# EthernetRMIIPHY.net
KiCad netlist of a schematic drawn in Altium Designer
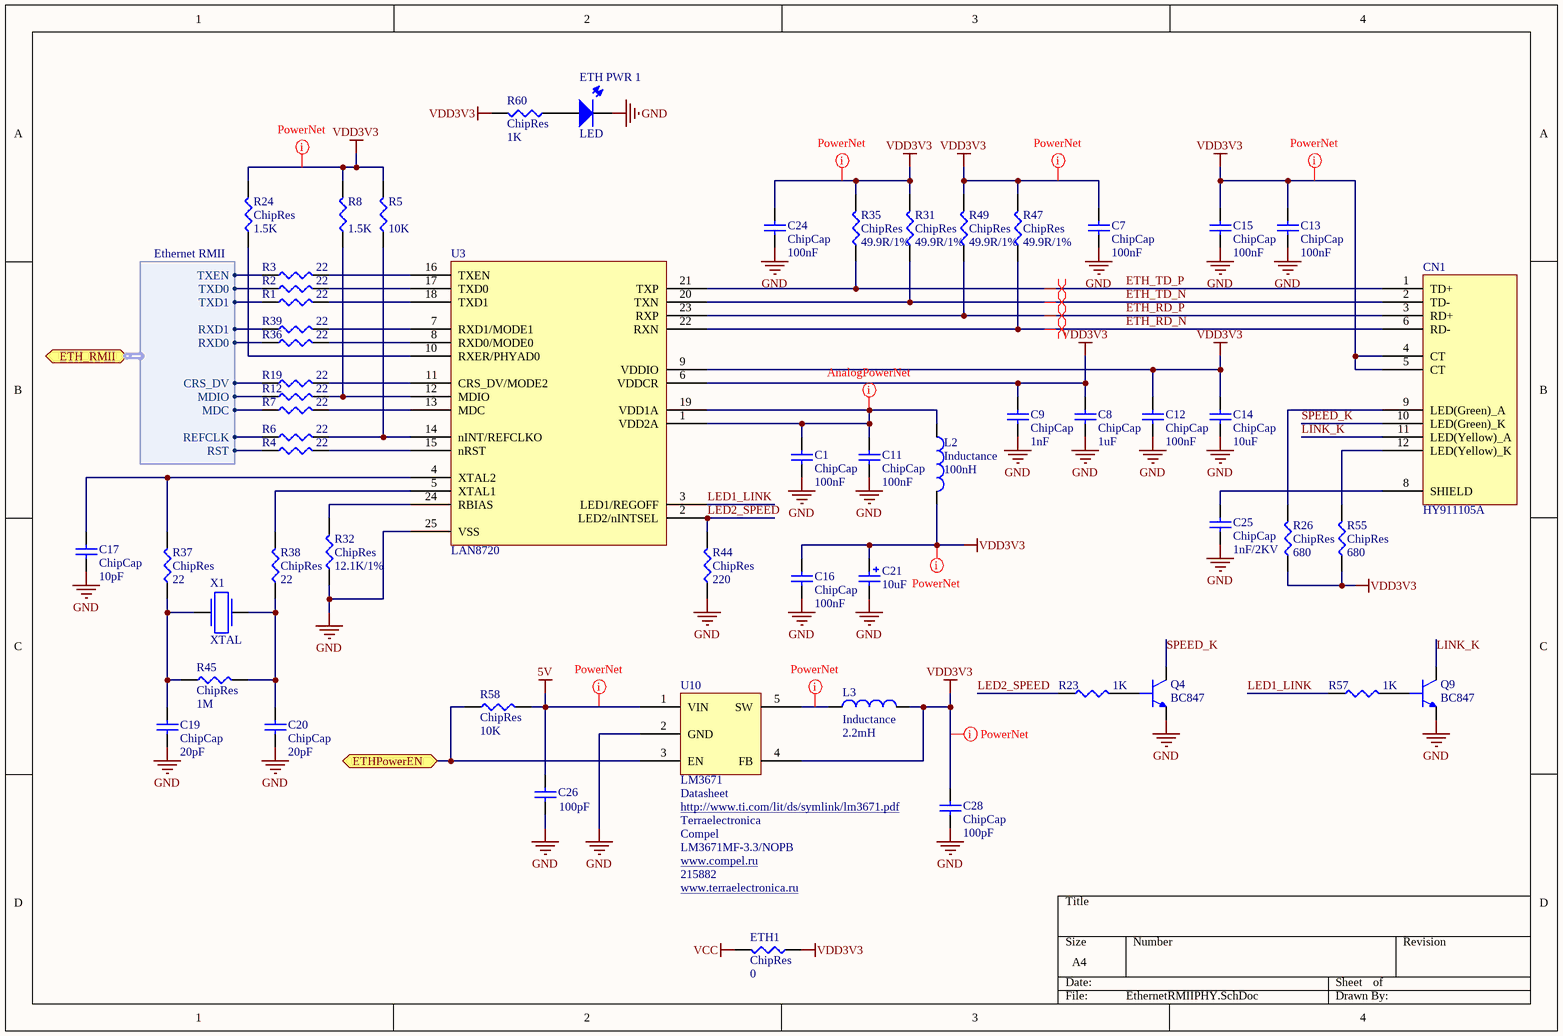
[diagram p0: EthernetRMIIPHY.SchDoc]

(export (version "E")
  (design (tool "Eeschema 10.0.6"))
  (components
    (comp (ref "C1")
      (value "ChipCap")
      (footprint "CAP0805")
      (description "Capacitor")
      (fields (field (name "ALTIUM_VALUE") "100nF") (field (name "PUBLISHER") "Altium Limited"))
      (libsource (lib "Common Devices") (part "ChipCap"))
    )
    (comp (ref "C7")
      (value "ChipCap")
      (footprint "CAP0805")
      (description "Capacitor")
      (fields (field (name "ALTIUM_VALUE") "100nF") (field (name "PUBLISHER") "Altium Limited"))
      (libsource (lib "Common Devices") (part "ChipCap"))
    )
    (comp (ref "C8")
      (value "ChipCap")
      (footprint "CAP0805")
      (description "Capacitor")
      (fields (field (name "ALTIUM_VALUE") "1uF") (field (name "PUBLISHER") "Altium Limited"))
      (libsource (lib "Common Devices") (part "ChipCap"))
    )
    (comp (ref "C9")
      (value "ChipCap")
      (footprint "CAP0805")
      (description "Capacitor")
      (fields (field (name "ALTIUM_VALUE") "1nF") (field (name "PUBLISHER") "Altium Limited"))
      (libsource (lib "Common Devices") (part "ChipCap"))
    )
    (comp (ref "C11")
      (value "ChipCap")
      (footprint "CAP0805")
      (description "Capacitor")
      (fields (field (name "ALTIUM_VALUE") "100nF") (field (name "PUBLISHER") "Altium Limited"))
      (libsource (lib "Common Devices") (part "ChipCap"))
    )
    (comp (ref "C12")
      (value "ChipCap")
      (footprint "CAP0805")
      (description "Capacitor")
      (fields (field (name "ALTIUM_VALUE") "100nF") (field (name "PUBLISHER") "Altium Limited"))
      (libsource (lib "Common Devices") (part "ChipCap"))
    )
    (comp (ref "C13")
      (value "ChipCap")
      (footprint "CAP0805")
      (description "Capacitor")
      (fields (field (name "ALTIUM_VALUE") "100nF") (field (name "PUBLISHER") "Altium Limited"))
      (libsource (lib "Common Devices") (part "ChipCap"))
    )
    (comp (ref "C14")
      (value "ChipCap")
      (footprint "CAP0805")
      (description "Capacitor")
      (fields (field (name "ALTIUM_VALUE") "10uF") (field (name "PUBLISHER") "Altium Limited"))
      (libsource (lib "Common Devices") (part "ChipCap"))
    )
    (comp (ref "C15")
      (value "ChipCap")
      (footprint "CAP0805")
      (description "Capacitor")
      (fields (field (name "ALTIUM_VALUE") "100nF") (field (name "PUBLISHER") "Altium Limited"))
      (libsource (lib "Common Devices") (part "ChipCap"))
    )
    (comp (ref "C16")
      (value "ChipCap")
      (footprint "CAP0805")
      (description "Capacitor")
      (fields (field (name "ALTIUM_VALUE") "100nF") (field (name "PUBLISHER") "Altium Limited"))
      (libsource (lib "Common Devices") (part "ChipCap"))
    )
    (comp (ref "C17")
      (value "ChipCap")
      (footprint "CAP0805")
      (description "Capacitor")
      (fields (field (name "ALTIUM_VALUE") "10pF") (field (name "PUBLISHER") "Altium Limited"))
      (libsource (lib "Common Devices") (part "ChipCap"))
    )
    (comp (ref "C19")
      (value "ChipCap")
      (footprint "CAP0805")
      (description "Capacitor")
      (fields (field (name "ALTIUM_VALUE") "20pF") (field (name "PUBLISHER") "Altium Limited"))
      (libsource (lib "Common Devices") (part "ChipCap"))
    )
    (comp (ref "C20")
      (value "ChipCap")
      (footprint "CAP0805")
      (description "Capacitor")
      (fields (field (name "ALTIUM_VALUE") "20pF") (field (name "PUBLISHER") "Altium Limited"))
      (libsource (lib "Common Devices") (part "ChipCap"))
    )
    (comp (ref "C21")
      (value "10uF")
      (footprint "CAPC7343")
      (description "Polarized Capacitor (Radial)")
      (fields (field (name "Comment") "Cap Pol SMD"))
      (libsource (lib "Common Devices") (part "Cap Pol Chip"))
    )
    (comp (ref "C24")
      (value "ChipCap")
      (footprint "CAP0805")
      (description "Capacitor")
      (fields (field (name "ALTIUM_VALUE") "100nF") (field (name "PUBLISHER") "Altium Limited"))
      (libsource (lib "Common Devices") (part "ChipCap"))
    )
    (comp (ref "C25")
      (value "ChipCap")
      (footprint "CAP0805")
      (description "Capacitor")
      (fields (field (name "ALTIUM_VALUE") "1nF/2KV") (field (name "PUBLISHER") "Altium Limited"))
      (libsource (lib "Common Devices") (part "ChipCap"))
    )
    (comp (ref "C26")
      (value "100pF")
      (footprint "CAP1210")
      (description "Capacitor")
      (fields (field (name "Comment") "ChipCap") (field (name "PUBLISHER") "Altium Limited"))
      (libsource (lib "Common Devices") (part "ChipCap"))
    )
    (comp (ref "C28")
      (value "ChipCap")
      (footprint "CAP1210")
      (description "Capacitor")
      (fields (field (name "ALTIUM_VALUE") "100pF") (field (name "PUBLISHER") "Altium Limited"))
      (libsource (lib "Common Devices") (part "ChipCap"))
    )
    (comp (ref "CN1")
      (value "HY911105A")
      (footprint "HR911105A")
      (libsource (lib "Connectors") (part "HY911105A"))
    )
    (comp (ref "ETH PWR 1") (value "LED") (footprint "PLCC-2") (libsource (lib "LEDs") (part "LED0603")))
    (comp (ref "ETH1")
      (value "ChipRes")
      (footprint "RES0805")
      (description "Chip resistor")
      (fields (field (name "ALTIUM_VALUE") "0"))
      (libsource (lib "Common Devices") (part "ChipRes"))
    )
    (comp (ref "L2")
      (value "Inductance")
      (footprint "CM45")
      (fields (field (name "ALTIUM_VALUE") "100nH"))
      (libsource (lib "") (part "ChipInductance_1"))
    )
    (comp (ref "L3")
      (value "Inductance")
      (footprint "CDRH2D14")
      (fields (field (name "ALTIUM_VALUE") "2.2mH"))
      (libsource (lib "Common Devices") (part "ChipInductance"))
    )
    (comp (ref "Q4")
      (value "BC847")
      (footprint "BJT:SOT23")
      (description "NPN transistor")
      (libsource (lib "BJT") (part "BC847"))
    )
    (comp (ref "Q9")
      (value "BC847")
      (footprint "BJT:SOT23")
      (description "NPN transistor")
      (libsource (lib "BJT") (part "BC847"))
    )
    (comp (ref "R1")
      (value "22")
      (footprint "RES0805")
      (description "Chip resistor")
      (fields (field (name "Comment") "ChipRes"))
      (libsource (lib "Common Devices") (part "ChipRes"))
    )
    (comp (ref "R2")
      (value "22")
      (footprint "RES0805")
      (description "Chip resistor")
      (fields (field (name "Comment") "ChipRes"))
      (libsource (lib "Common Devices") (part "ChipRes"))
    )
    (comp (ref "R3")
      (value "22")
      (footprint "RES0805")
      (description "Chip resistor")
      (fields (field (name "Comment") "ChipRes"))
      (libsource (lib "Common Devices") (part "ChipRes"))
    )
    (comp (ref "R4")
      (value "22")
      (footprint "RES0805")
      (description "Chip resistor")
      (fields (field (name "Comment") "ChipRes"))
      (libsource (lib "Common Devices") (part "ChipRes"))
    )
    (comp (ref "R5")
      (value "10K")
      (footprint "RES0805")
      (description "Chip resistor")
      (fields (field (name "Comment") "ChipRes"))
      (libsource (lib "Common Devices") (part "ChipRes"))
    )
    (comp (ref "R6")
      (value "22")
      (footprint "RES0805")
      (description "Chip resistor")
      (fields (field (name "Comment") "ChipRes"))
      (libsource (lib "Common Devices") (part "ChipRes"))
    )
    (comp (ref "R7")
      (value "22")
      (footprint "RES0805")
      (description "Chip resistor")
      (fields (field (name "Comment") "ChipRes"))
      (libsource (lib "Common Devices") (part "ChipRes"))
    )
    (comp (ref "R8")
      (value "1.5K")
      (footprint "RES0805")
      (description "Chip resistor")
      (fields (field (name "Comment") "ChipRes"))
      (libsource (lib "Common Devices") (part "ChipRes"))
    )
    (comp (ref "R12")
      (value "22")
      (footprint "RES0805")
      (description "Chip resistor")
      (fields (field (name "Comment") "ChipRes"))
      (libsource (lib "Common Devices") (part "ChipRes"))
    )
    (comp (ref "R19")
      (value "22")
      (footprint "RES0805")
      (description "Chip resistor")
      (fields (field (name "Comment") "ChipRes"))
      (libsource (lib "Common Devices") (part "ChipRes"))
    )
    (comp (ref "R23")
      (value "1K")
      (footprint "RES0805")
      (description "Chip resistor")
      (fields (field (name "Comment") "ChipRes"))
      (libsource (lib "Common Devices") (part "ChipRes"))
    )
    (comp (ref "R24")
      (value "ChipRes")
      (footprint "RES0805")
      (description "Chip resistor")
      (fields (field (name "ALTIUM_VALUE") "1.5K"))
      (libsource (lib "Common Devices") (part "ChipRes"))
    )
    (comp (ref "R26")
      (value "ChipRes")
      (footprint "RES0805")
      (description "Chip resistor")
      (fields (field (name "ALTIUM_VALUE") "680"))
      (libsource (lib "Common Devices") (part "ChipRes"))
    )
    (comp (ref "R31")
      (value "ChipRes")
      (footprint "RES0805")
      (description "Chip resistor")
      (fields (field (name "ALTIUM_VALUE") "49.9R/1%"))
      (libsource (lib "Common Devices") (part "ChipRes"))
    )
    (comp (ref "R32")
      (value "ChipRes")
      (footprint "RES0805")
      (description "Chip resistor")
      (fields (field (name "ALTIUM_VALUE") "12.1K/1%"))
      (libsource (lib "Common Devices") (part "ChipRes"))
    )
    (comp (ref "R35")
      (value "ChipRes")
      (footprint "RES0805")
      (description "Chip resistor")
      (fields (field (name "ALTIUM_VALUE") "49.9R/1%"))
      (libsource (lib "Common Devices") (part "ChipRes"))
    )
    (comp (ref "R36")
      (value "22")
      (footprint "RES0805")
      (description "Chip resistor")
      (fields (field (name "Comment") "ChipRes"))
      (libsource (lib "Common Devices") (part "ChipRes"))
    )
    (comp (ref "R37")
      (value "ChipRes")
      (footprint "RES0805")
      (description "Chip resistor")
      (fields (field (name "ALTIUM_VALUE") "22"))
      (libsource (lib "Common Devices") (part "ChipRes"))
    )
    (comp (ref "R38")
      (value "ChipRes")
      (footprint "RES0805")
      (description "Chip resistor")
      (fields (field (name "ALTIUM_VALUE") "22"))
      (libsource (lib "Common Devices") (part "ChipRes"))
    )
    (comp (ref "R39")
      (value "22")
      (footprint "RES0805")
      (description "Chip resistor")
      (fields (field (name "Comment") "ChipRes"))
      (libsource (lib "Common Devices") (part "ChipRes"))
    )
    (comp (ref "R44")
      (value "ChipRes")
      (footprint "RES0805")
      (description "Chip resistor")
      (fields (field (name "ALTIUM_VALUE") "220"))
      (libsource (lib "Common Devices") (part "ChipRes"))
    )
    (comp (ref "R45")
      (value "ChipRes")
      (footprint "RES0805")
      (description "Chip resistor")
      (fields (field (name "ALTIUM_VALUE") "1M"))
      (libsource (lib "Common Devices") (part "ChipRes"))
    )
    (comp (ref "R47")
      (value "ChipRes")
      (footprint "RES0805")
      (description "Chip resistor")
      (fields (field (name "ALTIUM_VALUE") "49.9R/1%"))
      (libsource (lib "Common Devices") (part "ChipRes"))
    )
    (comp (ref "R49")
      (value "ChipRes")
      (footprint "RES0805")
      (description "Chip resistor")
      (fields (field (name "ALTIUM_VALUE") "49.9R/1%"))
      (libsource (lib "Common Devices") (part "ChipRes"))
    )
    (comp (ref "R55")
      (value "ChipRes")
      (footprint "RES0805")
      (description "Chip resistor")
      (fields (field (name "ALTIUM_VALUE") "680"))
      (libsource (lib "Common Devices") (part "ChipRes"))
    )
    (comp (ref "R57")
      (value "1K")
      (footprint "RES0805")
      (description "Chip resistor")
      (fields (field (name "Comment") "ChipRes"))
      (libsource (lib "Common Devices") (part "ChipRes"))
    )
    (comp (ref "R58")
      (value "ChipRes")
      (footprint "RES0805")
      (description "Chip resistor")
      (fields (field (name "ALTIUM_VALUE") "10K"))
      (libsource (lib "Common Devices") (part "ChipRes"))
    )
    (comp (ref "R60")
      (value "ChipRes")
      (footprint "RES0805")
      (description "Chip resistor")
      (fields (field (name "ALTIUM_VALUE") "1K"))
      (libsource (lib "Common Devices") (part "ChipRes"))
    )
    (comp (ref "U3")
      (value "LAN8720")
      (footprint "QFN50P375X375X85_HS-25N")
      (description "Small Footprint RMII 10/100 Ethernet  Transceiver")
      (libsource (lib "SMSC Microchip Ethernet Driver") (part "LAM8720"))
    )
    (comp (ref "U10")
      (value "LM3671")
      (footprint "SOT23-5")
      (description "600-mA Step-Down DC-DC Converter")
      (fields
        (field (name "COMPONENTLINK1DESCRIPTION") "Datasheet")
        (field (name "COMPONENTLINK1URL") "http://www.ti.com/lit/ds/symlink/lm3671.pdf")
        (field (name "SUPPLIER 1") "Terraelectronica")
        (field (name "SUPPLIER 2") "Compel")
        (field (name "SUPPLIER PART NUMBER 2") "LM3671MF-3.3/NOPB")
        (field (name "SUPPLIER URL 2") "www.compel.ru")
        (field (name "SUPPLIER PART NUMBER 1") "215882")
        (field (name "SUPPLIER URL 1") "www.terraelectronica.ru")
      )
      (libsource (lib "TI DC-DC Convertors") (part "LM3671MF"))
    )
    (comp (ref "X1")
      (value "XTAL")
      (footprint "BCY-W2/E4.7")
      (description "Quartz crystall oscillator")
      (libsource (lib "Common Devices") (part "Crystall oscillator"))
    )
  )
  (nets
    (net (code "3") (name "/CRS_DV") (class "Default") (node (ref "R19") (pin "1") (pintype "passive")))
    (net (code "4") (name "/ETHPowerEN") (class "Default")
      (node (ref "R58") (pin "1") (pintype "passive"))
      (node (ref "U10") (pin "3") (pinfunction "EN_3") (pintype "passive"))
    )
    (net (code "5") (name "/ETH_RD_N") (class "Default")
      (node (ref "CN1") (pin "6") (pinfunction "RD-_6") (pintype "passive"))
      (node (ref "R47") (pin "1") (pintype "passive"))
      (node (ref "U3") (pin "22") (pinfunction "RXN_22") (pintype "passive"))
    )
    (net (code "6") (name "/ETH_RD_P") (class "Default")
      (node (ref "CN1") (pin "3") (pinfunction "RD+_3") (pintype "passive"))
      (node (ref "R49") (pin "1") (pintype "passive"))
      (node (ref "U3") (pin "23") (pinfunction "RXP_23") (pintype "passive"))
    )
    (net (code "7") (name "/ETH_TD_N") (class "Default")
      (node (ref "CN1") (pin "2") (pinfunction "TD-_2") (pintype "passive"))
      (node (ref "R31") (pin "1") (pintype "passive"))
      (node (ref "U3") (pin "20") (pinfunction "TXN_20") (pintype "passive"))
    )
    (net (code "8") (name "/ETH_TD_P") (class "Default")
      (node (ref "CN1") (pin "1") (pinfunction "TD+_1") (pintype "passive"))
      (node (ref "R35") (pin "1") (pintype "passive"))
      (node (ref "U3") (pin "21") (pinfunction "TXP_21") (pintype "passive"))
    )
    (net (code "9") (name "/LED1_LINK") (class "Default")
      (node (ref "R57") (pin "1") (pintype "passive"))
      (node (ref "U3") (pin "3") (pinfunction "LED1/REGOFF_3") (pintype "passive"))
    )
    (net (code "10") (name "/LED2_SPEED") (class "Default")
      (node (ref "R23") (pin "1") (pintype "passive"))
      (node (ref "R44") (pin "2") (pintype "passive"))
      (node (ref "U3") (pin "2") (pinfunction "LED2/nINTSEL_2") (pintype "passive"))
    )
    (net (code "11") (name "/LINK_K") (class "Default")
      (node (ref "CN1") (pin "11") (pinfunction "LED(Yellow)_A_11") (pintype "passive"))
      (node (ref "Q9") (pin "3") (pinfunction "3_3") (pintype "passive"))
    )
    (net (code "12") (name "/MDC") (class "Default") (node (ref "R7") (pin "1") (pintype "passive")))
    (net (code "13") (name "/MDIO") (class "Default") (node (ref "R12") (pin "1") (pintype "passive")))
    (net (code "14") (name "/REFCLK") (class "Default") (node (ref "R6") (pin "1") (pintype "passive")))
    (net (code "15") (name "/RST") (class "Default") (node (ref "R4") (pin "1") (pintype "passive")))
    (net (code "16") (name "/RXD0") (class "Default") (node (ref "R36") (pin "1") (pintype "passive")))
    (net (code "17") (name "/RXD1") (class "Default") (node (ref "R39") (pin "1") (pintype "passive")))
    (net (code "18") (name "/SPEED_K") (class "Default")
      (node (ref "CN1") (pin "10") (pinfunction "LED(Green)_K_10") (pintype "passive"))
      (node (ref "Q4") (pin "3") (pinfunction "3_3") (pintype "passive"))
    )
    (net (code "19") (name "/TXD0") (class "Default") (node (ref "R2") (pin "1") (pintype "passive")))
    (net (code "20") (name "/TXD1") (class "Default") (node (ref "R1") (pin "1") (pintype "passive")))
    (net (code "21") (name "/TXEN") (class "Default") (node (ref "R3") (pin "1") (pintype "passive")))
    (net (code "23") (name "5V") (class "Default")
      (node (ref "C26") (pin "2") (pinfunction "2_2") (pintype "passive"))
      (node (ref "R58") (pin "2") (pintype "passive"))
      (node (ref "U10") (pin "1") (pinfunction "VIN_1") (pintype "passive"))
    )
    (net (code "24") (name "GND") (class "Default")
      (node (ref "C1") (pin "1") (pinfunction "1_1") (pintype "passive"))
      (node (ref "C11") (pin "1") (pinfunction "1_1") (pintype "passive"))
      (node (ref "C12") (pin "1") (pinfunction "1_1") (pintype "passive"))
      (node (ref "C13") (pin "1") (pinfunction "1_1") (pintype "passive"))
      (node (ref "C14") (pin "1") (pinfunction "1_1") (pintype "passive"))
      (node (ref "C15") (pin "1") (pinfunction "1_1") (pintype "passive"))
      (node (ref "C16") (pin "1") (pinfunction "1_1") (pintype "passive"))
      (node (ref "C17") (pin "1") (pinfunction "1_1") (pintype "passive"))
      (node (ref "C19") (pin "1") (pinfunction "1_1") (pintype "passive"))
      (node (ref "C20") (pin "1") (pinfunction "1_1") (pintype "passive"))
      (node (ref "C21") (pin "2") (pinfunction "2_2") (pintype "passive"))
      (node (ref "C24") (pin "1") (pinfunction "1_1") (pintype "passive"))
      (node (ref "C25") (pin "1") (pinfunction "1_1") (pintype "passive"))
      (node (ref "C26") (pin "1") (pinfunction "1_1") (pintype "passive"))
      (node (ref "C28") (pin "1") (pinfunction "1_1") (pintype "passive"))
      (node (ref "C7") (pin "1") (pinfunction "1_1") (pintype "passive"))
      (node (ref "C8") (pin "1") (pinfunction "1_1") (pintype "passive"))
      (node (ref "C9") (pin "1") (pinfunction "1_1") (pintype "passive"))
      (node (ref "ETH PWR 1") (pin "1") (pinfunction "1_1") (pintype "passive"))
      (node (ref "Q4") (pin "2") (pinfunction "2_2") (pintype "passive"))
      (node (ref "Q9") (pin "2") (pinfunction "2_2") (pintype "passive"))
      (node (ref "R32") (pin "1") (pintype "passive"))
      (node (ref "R44") (pin "1") (pintype "passive"))
      (node (ref "U10") (pin "2") (pinfunction "GND_2") (pintype "passive"))
      (node (ref "U3") (pin "25") (pinfunction "VSS_25") (pintype "passive"))
    )
    (net (code "25") (name "Net-(C19-Pad2)") (class "Default")
      (node (ref "C19") (pin "2") (pinfunction "2_2") (pintype "passive"))
      (node (ref "R37") (pin "1") (pintype "passive"))
      (node (ref "R45") (pin "1") (pintype "passive"))
      (node (ref "X1") (pin "1") (pinfunction "1_1") (pintype "passive"))
    )
    (net (code "26") (name "Net-(C20-Pad2)") (class "Default")
      (node (ref "C20") (pin "2") (pinfunction "2_2") (pintype "passive"))
      (node (ref "R38") (pin "1") (pintype "passive"))
      (node (ref "R45") (pin "2") (pintype "passive"))
      (node (ref "X1") (pin "2") (pinfunction "2_2") (pintype "passive"))
    )
    (net (code "27") (name "Net-(CN1-LED(Green)_A)") (class "Default")
      (node (ref "CN1") (pin "9") (pinfunction "LED(Green)_A_9") (pintype "passive"))
      (node (ref "R26") (pin "2") (pintype "passive"))
    )
    (net (code "28") (name "Net-(CN1-LED(Yellow)_K)") (class "Default")
      (node (ref "CN1") (pin "12") (pinfunction "LED(Yellow)_K_12") (pintype "passive"))
      (node (ref "R55") (pin "2") (pintype "passive"))
    )
    (net (code "29") (name "Net-(CN1-SHIELD)") (class "Default")
      (node (ref "C25") (pin "2") (pinfunction "2_2") (pintype "passive"))
      (node (ref "CN1") (pin "8") (pinfunction "SHIELD_8") (pintype "passive"))
    )
    (net (code "30") (name "Net-(ETH PWR 1-Pad2)") (class "Default")
      (node (ref "ETH PWR 1") (pin "2") (pinfunction "2_2") (pintype "passive"))
      (node (ref "R60") (pin "1") (pintype "passive"))
    )
    (net (code "31") (name "Net-(Q4-Pad1)") (class "Default")
      (node (ref "Q4") (pin "1") (pinfunction "1_1") (pintype "passive"))
      (node (ref "R23") (pin "2") (pintype "passive"))
    )
    (net (code "32") (name "Net-(Q9-Pad1)") (class "Default")
      (node (ref "Q9") (pin "1") (pinfunction "1_1") (pintype "passive"))
      (node (ref "R57") (pin "2") (pintype "passive"))
    )
    (net (code "33") (name "Net-(U3-CRS_DV{slash}MODE2)") (class "Default")
      (node (ref "R19") (pin "2") (pintype "passive"))
      (node (ref "U3") (pin "11") (pinfunction "CRS_DV/MODE2_11") (pintype "passive"))
    )
    (net (code "34") (name "Net-(U3-MDC)") (class "Default")
      (node (ref "R7") (pin "2") (pintype "passive"))
      (node (ref "U3") (pin "13") (pinfunction "MDC_13") (pintype "passive"))
    )
    (net (code "35") (name "Net-(U3-MDIO)") (class "Default")
      (node (ref "R12") (pin "2") (pintype "passive"))
      (node (ref "R8") (pin "1") (pintype "passive"))
      (node (ref "U3") (pin "12") (pinfunction "MDIO_12") (pintype "passive"))
    )
    (net (code "36") (name "Net-(U3-RBIAS)") (class "Default")
      (node (ref "R32") (pin "2") (pintype "passive"))
      (node (ref "U3") (pin "24") (pinfunction "RBIAS_24") (pintype "passive"))
    )
    (net (code "37") (name "Net-(U3-RXD0{slash}MODE0)") (class "Default")
      (node (ref "R36") (pin "2") (pintype "passive"))
      (node (ref "U3") (pin "8") (pinfunction "RXD0/MODE0_8") (pintype "passive"))
    )
    (net (code "38") (name "Net-(U3-RXD1{slash}MODE1)") (class "Default")
      (node (ref "R39") (pin "2") (pintype "passive"))
      (node (ref "U3") (pin "7") (pinfunction "RXD1/MODE1_7") (pintype "passive"))
    )
    (net (code "39") (name "Net-(U3-RXER{slash}PHYAD0)") (class "Default")
      (node (ref "R24") (pin "1") (pintype "passive"))
      (node (ref "U3") (pin "10") (pinfunction "RXER/PHYAD0_10") (pintype "passive"))
    )
    (net (code "40") (name "Net-(U3-TXD0)") (class "Default")
      (node (ref "R2") (pin "2") (pintype "passive"))
      (node (ref "U3") (pin "17") (pinfunction "TXD0_17") (pintype "passive"))
    )
    (net (code "41") (name "Net-(U3-TXD1)") (class "Default")
      (node (ref "R1") (pin "2") (pintype "passive"))
      (node (ref "U3") (pin "18") (pinfunction "TXD1_18") (pintype "passive"))
    )
    (net (code "42") (name "Net-(U3-TXEN)") (class "Default")
      (node (ref "R3") (pin "2") (pintype "passive"))
      (node (ref "U3") (pin "16") (pinfunction "TXEN_16") (pintype "passive"))
    )
    (net (code "43") (name "Net-(U3-VDD1A)") (class "Default")
      (node (ref "C1") (pin "2") (pinfunction "2_2") (pintype "passive"))
      (node (ref "C11") (pin "2") (pinfunction "2_2") (pintype "passive"))
      (node (ref "L2") (pin "2") (pintype "passive"))
      (node (ref "U3") (pin "1") (pinfunction "VDD2A_1") (pintype "passive"))
      (node (ref "U3") (pin "19") (pinfunction "VDD1A_19") (pintype "passive"))
    )
    (net (code "44") (name "Net-(U3-XTAL1)") (class "Default")
      (node (ref "R38") (pin "2") (pintype "passive"))
      (node (ref "U3") (pin "5") (pinfunction "XTAL1_5") (pintype "passive"))
    )
    (net (code "45") (name "Net-(U3-XTAL2)") (class "Default")
      (node (ref "C17") (pin "2") (pinfunction "2_2") (pintype "passive"))
      (node (ref "R37") (pin "2") (pintype "passive"))
      (node (ref "U3") (pin "4") (pinfunction "XTAL2_4") (pintype "passive"))
    )
    (net (code "46") (name "Net-(U3-nINT{slash}REFCLKO)") (class "Default")
      (node (ref "R5") (pin "1") (pintype "passive"))
      (node (ref "R6") (pin "2") (pintype "passive"))
      (node (ref "U3") (pin "14") (pinfunction "nINT/REFCLKO_14") (pintype "passive"))
    )
    (net (code "47") (name "Net-(U3-nRST)") (class "Default")
      (node (ref "R4") (pin "2") (pintype "passive"))
      (node (ref "U3") (pin "15") (pinfunction "nRST_15") (pintype "passive"))
    )
    (net (code "48") (name "Net-(U10-SW)") (class "Default")
      (node (ref "L3") (pin "2") (pintype "passive"))
      (node (ref "U10") (pin "5") (pinfunction "SW_5") (pintype "passive"))
    )
    (net (code "49") (name "VCC") (class "Default") (node (ref "ETH1") (pin "2") (pintype "passive")))
    (net (code "50") (name "VDD3V3") (class "Default")
      (node (ref "C12") (pin "2") (pinfunction "2_2") (pintype "passive"))
      (node (ref "C13") (pin "2") (pinfunction "2_2") (pintype "passive"))
      (node (ref "C14") (pin "2") (pinfunction "2_2") (pintype "passive"))
      (node (ref "C15") (pin "2") (pinfunction "2_2") (pintype "passive"))
      (node (ref "C16") (pin "2") (pinfunction "2_2") (pintype "passive"))
      (node (ref "C21") (pin "1") (pinfunction "1_1") (pintype "passive"))
      (node (ref "C24") (pin "2") (pinfunction "2_2") (pintype "passive"))
      (node (ref "C28") (pin "2") (pinfunction "2_2") (pintype "passive"))
      (node (ref "C7") (pin "2") (pinfunction "2_2") (pintype "passive"))
      (node (ref "C8") (pin "2") (pinfunction "2_2") (pintype "passive"))
      (node (ref "C9") (pin "2") (pinfunction "2_2") (pintype "passive"))
      (node (ref "CN1") (pin "4") (pinfunction "CT_4") (pintype "passive"))
      (node (ref "CN1") (pin "5") (pinfunction "CT_5") (pintype "passive"))
      (node (ref "ETH1") (pin "1") (pintype "passive"))
      (node (ref "L2") (pin "1") (pintype "passive"))
      (node (ref "L3") (pin "1") (pintype "passive"))
      (node (ref "R24") (pin "2") (pintype "passive"))
      (node (ref "R26") (pin "1") (pintype "passive"))
      (node (ref "R31") (pin "2") (pintype "passive"))
      (node (ref "R35") (pin "2") (pintype "passive"))
      (node (ref "R47") (pin "2") (pintype "passive"))
      (node (ref "R49") (pin "2") (pintype "passive"))
      (node (ref "R5") (pin "2") (pintype "passive"))
      (node (ref "R55") (pin "1") (pintype "passive"))
      (node (ref "R60") (pin "2") (pintype "passive"))
      (node (ref "R8") (pin "2") (pintype "passive"))
      (node (ref "U10") (pin "4") (pinfunction "FB_4") (pintype "passive"))
      (node (ref "U3") (pin "6") (pinfunction "VDDCR_6") (pintype "passive"))
      (node (ref "U3") (pin "9") (pinfunction "VDDIO_9") (pintype "passive"))
    )
  )
)
